# LPC_Female_FMC.net
KiCad netlist of a schematic drawn in Altium Designer
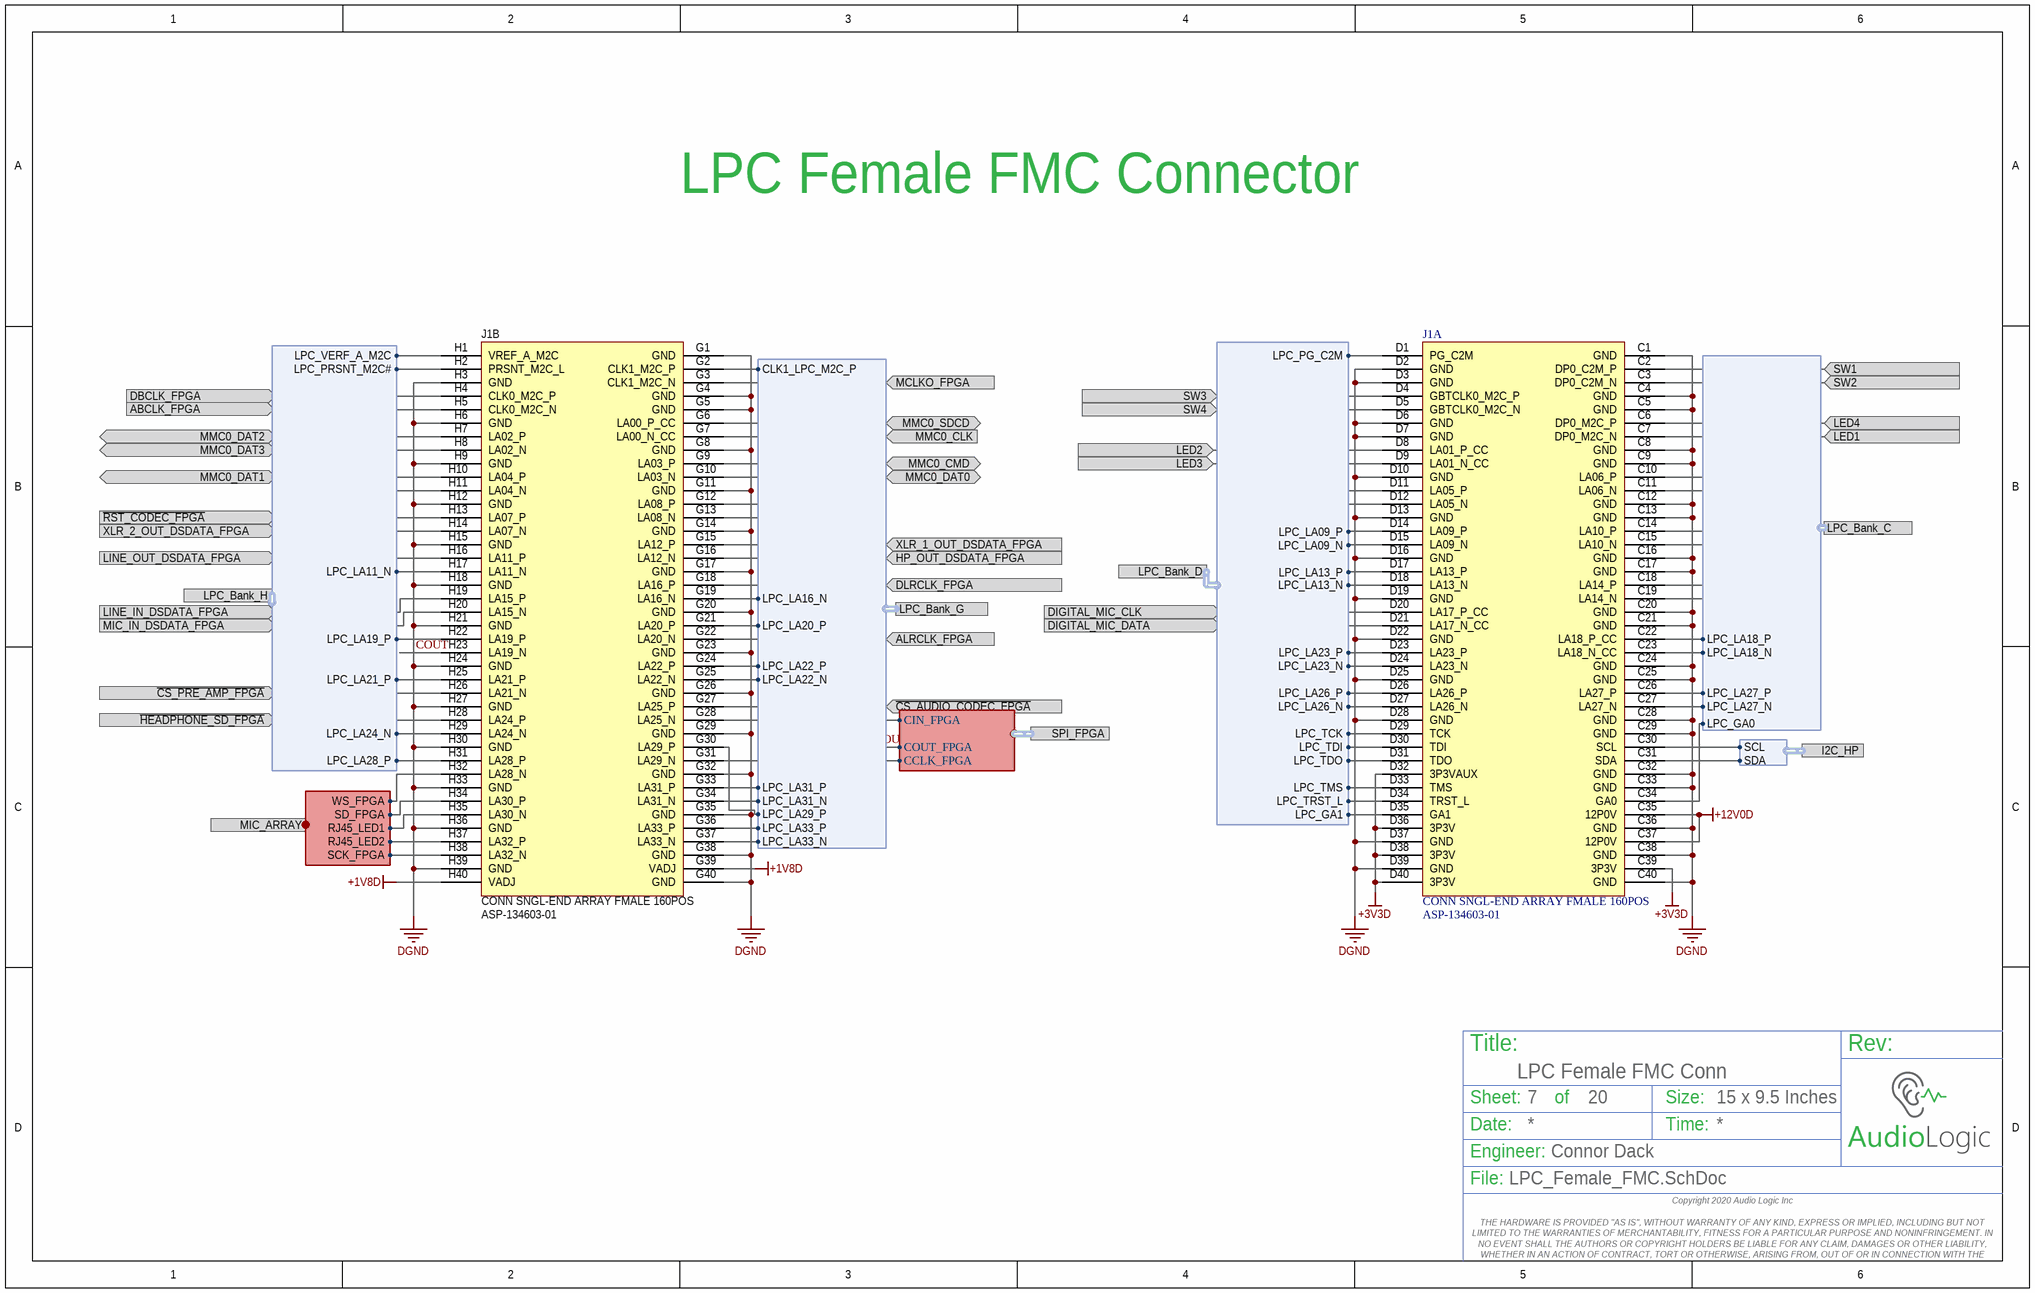
[diagram p0: LPC_Female_FMC.SchDoc]

(export (version "E")
  (design (tool "Eeschema 10.0.6"))
  (components
    (comp (ref "J1")
      (value "CONN SNGL-END ARRAY FMALE 160POS")
      (footprint "ASP-134603-01")
      (description "Low Pin Count Female FPGA Mezzanine Card Connector")
      (fields
        (field (name "MANUFACTURER") "Samtec")
        (field (name "MANUFACTURER PART NUMBER") "ASP-134603-01")
      )
      (libsource (lib "Schematic_Components_CD") (part "ASP-134603-01"))
    )
  )
  (nets
    (net (code "9") (name "+1V8D") (class "Default")
      (node (ref "J1") (pin "G39") (pinfunction "VADJ_G39") (pintype "power_in"))
      (node (ref "J1") (pin "H40") (pinfunction "VADJ_H40") (pintype "power_in"))
    )
    (net (code "10") (name "+3V3D") (class "Default")
      (node (ref "J1") (pin "C39") (pinfunction "3P3V_C39") (pintype "power_in"))
      (node (ref "J1") (pin "D32") (pinfunction "3P3VAUX_D32") (pintype "power_in"))
      (node (ref "J1") (pin "D36") (pinfunction "3P3V_D36") (pintype "power_in"))
      (node (ref "J1") (pin "D38") (pinfunction "3P3V_D38") (pintype "power_in"))
      (node (ref "J1") (pin "D40") (pinfunction "3P3V_D40") (pintype "power_in"))
    )
    (net (code "11") (name "+12V0D") (class "Default")
      (node (ref "J1") (pin "C10") (pinfunction "LA06_P_C10") (pintype "passive"))
      (node (ref "J1") (pin "C11") (pinfunction "LA06_N_C11") (pintype "passive"))
      (node (ref "J1") (pin "C35") (pinfunction "12P0V_C35") (pintype "power_in"))
      (node (ref "J1") (pin "C37") (pinfunction "12P0V_C37") (pintype "power_in"))
      (node (ref "J1") (pin "D11") (pinfunction "LA05_P_D11") (pintype "passive"))
      (node (ref "J1") (pin "D12") (pinfunction "LA05_N_D12") (pintype "passive"))
      (node (ref "J1") (pin "G12") (pinfunction "LA08_P_G12") (pintype "passive"))
      (node (ref "J1") (pin "G13") (pinfunction "LA08_N_G13") (pintype "passive"))
      (node (ref "J1") (pin "H11") (pinfunction "LA04_N_H11") (pintype "passive"))
    )
    (net (code "12") (name "/ABCLK_FPGA") (class "Default")
      (node (ref "J1") (pin "H5") (pinfunction "CLK0_M2C_N_H5") (pintype "passive"))
    )
    (net (code "13") (name "/ALRCLK_FPGA") (class "Default")
      (node (ref "J1") (pin "G22") (pinfunction "LA20_N_G22") (pintype "passive"))
    )
    (net (code "14") (name "/CCLK_FPGA") (class "Default")
      (node (ref "J1") (pin "G31") (pinfunction "LA29_N_G31") (pintype "passive"))
    )
    (net (code "15") (name "/CIN_FPGA") (class "Default")
      (node (ref "J1") (pin "G28") (pinfunction "LA25_N_G28") (pintype "passive"))
    )
    (net (code "16") (name "/CLK1_LPC_M2C_P") (class "Default")
      (node (ref "J1") (pin "G2") (pinfunction "CLK1_M2C_P_G2") (pintype "passive"))
    )
    (net (code "17") (name "/CMD_DIR1") (class "Default")
      (node (ref "J1") (pin "C19") (pinfunction "LA14_N_C19") (pintype "passive"))
    )
    (net (code "18") (name "/CMD_DIR2") (class "Default")
      (node (ref "J1") (pin "C18") (pinfunction "LA14_P_C18") (pintype "passive"))
    )
    (net (code "19") (name "/COUT") (class "Default")
      (node (ref "J1") (pin "H23") (pinfunction "LA19_N_H23") (pintype "passive"))
    )
    (net (code "20") (name "/DATA_DIR1") (class "Default")
      (node (ref "J1") (pin "C15") (pinfunction "LA10_N_C15") (pintype "passive"))
    )
    (net (code "21") (name "/DATA_DIR2") (class "Default")
      (node (ref "J1") (pin "C14") (pinfunction "LA10_P_C14") (pintype "passive"))
    )
    (net (code "22") (name "/DBCLK_FPGA") (class "Default")
      (node (ref "J1") (pin "H4") (pinfunction "CLK0_M2C_P_H4") (pintype "passive"))
    )
    (net (code "23") (name "/DIGITAL_MIC_CLK") (class "Default")
      (node (ref "J1") (pin "D20") (pinfunction "LA17_P_CC_D20") (pintype "passive"))
    )
    (net (code "24") (name "/DIGITAL_MIC_DATA") (class "Default")
      (node (ref "J1") (pin "D21") (pinfunction "LA17_N_CC_D21") (pintype "passive"))
    )
    (net (code "25") (name "/DLRCLK_FPGA") (class "Default")
      (node (ref "J1") (pin "G18") (pinfunction "LA16_P_G18") (pintype "passive"))
    )
    (net (code "26") (name "/HP_OUT_DSDATA_FPGA") (class "Default")
      (node (ref "J1") (pin "G16") (pinfunction "LA12_N_G16") (pintype "passive"))
    )
    (net (code "27") (name "/LED1") (class "Default")
      (node (ref "J1") (pin "C7") (pinfunction "DP0_M2C_N_C7") (pintype "passive"))
    )
    (net (code "28") (name "/LED2") (class "Default")
      (node (ref "J1") (pin "D8") (pinfunction "LA01_P_CC_D8") (pintype "passive"))
    )
    (net (code "29") (name "/LED3") (class "Default")
      (node (ref "J1") (pin "D9") (pinfunction "LA01_N_CC_D9") (pintype "passive"))
    )
    (net (code "30") (name "/LED4") (class "Default")
      (node (ref "J1") (pin "C6") (pinfunction "DP0_M2C_P_C6") (pintype "passive"))
    )
    (net (code "31") (name "/LINE_IN_DSDATA_FPGA") (class "Default")
      (node (ref "J1") (pin "H19") (pinfunction "LA15_P_H19") (pintype "passive"))
    )
    (net (code "32") (name "/LINE_OUT_DSDATA_FPGA") (class "Default")
      (node (ref "J1") (pin "H16") (pinfunction "LA11_P_H16") (pintype "passive"))
    )
    (net (code "33") (name "/LPC_GA0") (class "Default")
      (node (ref "J1") (pin "C34") (pinfunction "GA0_C34") (pintype "passive"))
    )
    (net (code "34") (name "/LPC_GA1") (class "Default")
      (node (ref "J1") (pin "D35") (pinfunction "GA1_D35") (pintype "passive"))
    )
    (net (code "35") (name "/LPC_LA09_N") (class "Default")
      (node (ref "J1") (pin "D15") (pinfunction "LA09_N_D15") (pintype "passive"))
    )
    (net (code "36") (name "/LPC_LA09_P") (class "Default")
      (node (ref "J1") (pin "D14") (pinfunction "LA09_P_D14") (pintype "passive"))
    )
    (net (code "37") (name "/LPC_LA11_N") (class "Default")
      (node (ref "J1") (pin "H17") (pinfunction "LA11_N_H17") (pintype "passive"))
    )
    (net (code "38") (name "/LPC_LA13_N") (class "Default")
      (node (ref "J1") (pin "D18") (pinfunction "LA13_N_D18") (pintype "passive"))
    )
    (net (code "39") (name "/LPC_LA13_P") (class "Default")
      (node (ref "J1") (pin "D17") (pinfunction "LA13_P_D17") (pintype "passive"))
    )
    (net (code "40") (name "/LPC_LA16_N") (class "Default")
      (node (ref "J1") (pin "G19") (pinfunction "LA16_N_G19") (pintype "passive"))
    )
    (net (code "41") (name "/LPC_LA18_N") (class "Default")
      (node (ref "J1") (pin "C23") (pinfunction "LA18_N_CC_C23") (pintype "passive"))
    )
    (net (code "42") (name "/LPC_LA18_P") (class "Default")
      (node (ref "J1") (pin "C22") (pinfunction "LA18_P_CC_C22") (pintype "passive"))
    )
    (net (code "43") (name "/LPC_LA19_P") (class "Default")
      (node (ref "J1") (pin "H22") (pinfunction "LA19_P_H22") (pintype "passive"))
    )
    (net (code "44") (name "/LPC_LA20_P") (class "Default")
      (node (ref "J1") (pin "G21") (pinfunction "LA20_P_G21") (pintype "passive"))
    )
    (net (code "45") (name "/LPC_LA21_P") (class "Default")
      (node (ref "J1") (pin "H25") (pinfunction "LA21_P_H25") (pintype "passive"))
    )
    (net (code "46") (name "/LPC_LA22_N") (class "Default")
      (node (ref "J1") (pin "G25") (pinfunction "LA22_N_G25") (pintype "passive"))
    )
    (net (code "47") (name "/LPC_LA22_P") (class "Default")
      (node (ref "J1") (pin "G24") (pinfunction "LA22_P_G24") (pintype "passive"))
    )
    (net (code "48") (name "/LPC_LA23_N") (class "Default")
      (node (ref "J1") (pin "D24") (pinfunction "LA23_N_D24") (pintype "passive"))
    )
    (net (code "49") (name "/LPC_LA23_P") (class "Default")
      (node (ref "J1") (pin "D23") (pinfunction "LA23_P_D23") (pintype "passive"))
    )
    (net (code "50") (name "/LPC_LA24_N") (class "Default")
      (node (ref "J1") (pin "H29") (pinfunction "LA24_N_H29") (pintype "passive"))
    )
    (net (code "51") (name "/LPC_LA26_N") (class "Default")
      (node (ref "J1") (pin "D27") (pinfunction "LA26_N_D27") (pintype "passive"))
    )
    (net (code "52") (name "/LPC_LA26_P") (class "Default")
      (node (ref "J1") (pin "D26") (pinfunction "LA26_P_D26") (pintype "passive"))
    )
    (net (code "53") (name "/LPC_LA27_N") (class "Default")
      (node (ref "J1") (pin "C27") (pinfunction "LA27_N_C27") (pintype "passive"))
    )
    (net (code "54") (name "/LPC_LA27_P") (class "Default")
      (node (ref "J1") (pin "C26") (pinfunction "LA27_P_C26") (pintype "passive"))
    )
    (net (code "55") (name "/LPC_LA28_P") (class "Default")
      (node (ref "J1") (pin "H31") (pinfunction "LA28_P_H31") (pintype "passive"))
    )
    (net (code "56") (name "/LPC_LA29_P") (class "Default")
      (node (ref "J1") (pin "G30") (pinfunction "LA29_P_G30") (pintype "passive"))
    )
    (net (code "57") (name "/LPC_LA31_N") (class "Default")
      (node (ref "J1") (pin "G34") (pinfunction "LA31_N_G34") (pintype "passive"))
    )
    (net (code "58") (name "/LPC_LA31_P") (class "Default")
      (node (ref "J1") (pin "G33") (pinfunction "LA31_P_G33") (pintype "passive"))
    )
    (net (code "59") (name "/LPC_LA33_N") (class "Default")
      (node (ref "J1") (pin "G37") (pinfunction "LA33_N_G37") (pintype "passive"))
    )
    (net (code "60") (name "/LPC_LA33_P") (class "Default")
      (node (ref "J1") (pin "G36") (pinfunction "LA33_P_G36") (pintype "passive"))
    )
    (net (code "61") (name "/LPC_PG_C2M") (class "Default")
      (node (ref "J1") (pin "D1") (pinfunction "PG_C2M_D1") (pintype "passive"))
    )
    (net (code "62") (name "/LPC_PRSNT_M2C#") (class "Default")
      (node (ref "J1") (pin "H2") (pinfunction "PRSNT_M2C_L_H2") (pintype "passive"))
    )
    (net (code "63") (name "/LPC_TCK") (class "Default")
      (node (ref "J1") (pin "D29") (pinfunction "TCK_D29") (pintype "passive"))
    )
    (net (code "64") (name "/LPC_TDI") (class "Default")
      (node (ref "J1") (pin "D30") (pinfunction "TDI_D30") (pintype "passive"))
    )
    (net (code "65") (name "/LPC_TDO") (class "Default")
      (node (ref "J1") (pin "D31") (pinfunction "TDO_D31") (pintype "passive"))
    )
    (net (code "66") (name "/LPC_TMS") (class "Default")
      (node (ref "J1") (pin "D33") (pinfunction "TMS_D33") (pintype "passive"))
    )
    (net (code "67") (name "/LPC_TRST_L") (class "Default")
      (node (ref "J1") (pin "D34") (pinfunction "TRST_L_D34") (pintype "passive"))
    )
    (net (code "68") (name "/LPC_VERF_A_M2C") (class "Default")
      (node (ref "J1") (pin "H1") (pinfunction "VREF_A_M2C_H1") (pintype "power_in"))
    )
    (net (code "69") (name "/MCLKO_FPGA") (class "Default")
      (node (ref "J1") (pin "G3") (pinfunction "CLK1_M2C_N_G3") (pintype "passive"))
    )
    (net (code "70") (name "/MIC_IN_DSDATA_FPGA") (class "Default")
      (node (ref "J1") (pin "H20") (pinfunction "LA15_N_H20") (pintype "passive"))
    )
    (net (code "71") (name "/MMC0_CLK") (class "Default")
      (node (ref "J1") (pin "G7") (pinfunction "LA00_N_CC_G7") (pintype "passive"))
    )
    (net (code "72") (name "/MMC0_CMD") (class "Default")
      (node (ref "J1") (pin "G9") (pinfunction "LA03_P_G9") (pintype "passive"))
    )
    (net (code "73") (name "/MMC0_DAT0") (class "Default")
      (node (ref "J1") (pin "G10") (pinfunction "LA03_N_G10") (pintype "passive"))
    )
    (net (code "74") (name "/MMC0_DAT1") (class "Default")
      (node (ref "J1") (pin "H10") (pinfunction "LA04_P_H10") (pintype "passive"))
    )
    (net (code "75") (name "/MMC0_DAT2") (class "Default")
      (node (ref "J1") (pin "H7") (pinfunction "LA02_P_H7") (pintype "passive"))
    )
    (net (code "76") (name "/MMC0_DAT3") (class "Default")
      (node (ref "J1") (pin "H8") (pinfunction "LA02_N_H8") (pintype "passive"))
    )
    (net (code "77") (name "/MMC0_SDCD") (class "Default")
      (node (ref "J1") (pin "G6") (pinfunction "LA00_P_CC_G6") (pintype "passive"))
    )
    (net (code "78") (name "/RJ45_LED1") (class "Default")
      (node (ref "J1") (pin "H35") (pinfunction "LA30_N_H35") (pintype "passive"))
    )
    (net (code "79") (name "/RJ45_LED2") (class "Default")
      (node (ref "J1") (pin "H37") (pinfunction "LA32_P_H37") (pintype "passive"))
    )
    (net (code "80") (name "/SCK_FPGA") (class "Default")
      (node (ref "J1") (pin "H38") (pinfunction "LA32_N_H38") (pintype "passive"))
    )
    (net (code "81") (name "/SCL") (class "Default")
      (node (ref "J1") (pin "C30") (pinfunction "SCL_C30") (pintype "passive"))
    )
    (net (code "82") (name "/SDA") (class "Default")
      (node (ref "J1") (pin "C31") (pinfunction "SDA_C31") (pintype "passive"))
    )
    (net (code "83") (name "/SD_FPGA") (class "Default")
      (node (ref "J1") (pin "H34") (pinfunction "LA30_P_H34") (pintype "passive"))
    )
    (net (code "84") (name "/SW1") (class "Default")
      (node (ref "J1") (pin "C2") (pinfunction "DP0_C2M_P_C2") (pintype "passive"))
    )
    (net (code "85") (name "/SW2") (class "Default")
      (node (ref "J1") (pin "C3") (pinfunction "DP0_C2M_N_C3") (pintype "passive"))
    )
    (net (code "86") (name "/SW3") (class "Default")
      (node (ref "J1") (pin "D4") (pinfunction "GBTCLK0_M2C_P_D4") (pintype "passive"))
    )
    (net (code "87") (name "/SW4") (class "Default")
      (node (ref "J1") (pin "D5") (pinfunction "GBTCLK0_M2C_N_D5") (pintype "passive"))
    )
    (net (code "88") (name "/WS_FPGA") (class "Default")
      (node (ref "J1") (pin "H32") (pinfunction "LA28_N_H32") (pintype "passive"))
    )
    (net (code "89") (name "/XLR_1_OUT_DSDATA_FPGA") (class "Default")
      (node (ref "J1") (pin "G15") (pinfunction "LA12_P_G15") (pintype "passive"))
    )
    (net (code "90") (name "/XLR_2_OUT_DSDATA_FPGA") (class "Default")
      (node (ref "J1") (pin "H14") (pinfunction "LA07_N_H14") (pintype "passive"))
    )
    (net (code "98") (name "/~{CS_AUDIO_CODEC_FPGA}") (class "Default")
      (node (ref "J1") (pin "G27") (pinfunction "LA25_P_G27") (pintype "passive"))
    )
    (net (code "99") (name "/~{CS_PRE_AMP_FPGA}") (class "Default")
      (node (ref "J1") (pin "H26") (pinfunction "LA21_N_H26") (pintype "passive"))
    )
    (net (code "100") (name "/~{HEADPHONE_SD_FPGA}") (class "Default")
      (node (ref "J1") (pin "H28") (pinfunction "LA24_P_H28") (pintype "passive"))
    )
    (net (code "101") (name "/~{RST_CODEC_FPGA}") (class "Default")
      (node (ref "J1") (pin "H13") (pinfunction "LA07_P_H13") (pintype "passive"))
    )
    (net (code "102") (name "DGND") (class "Default")
      (node (ref "J1") (pin "C1") (pinfunction "GND_C1") (pintype "power_in"))
      (node (ref "J1") (pin "C12") (pinfunction "GND_C12") (pintype "power_in"))
      (node (ref "J1") (pin "C13") (pinfunction "GND_C13") (pintype "power_in"))
      (node (ref "J1") (pin "C16") (pinfunction "GND_C16") (pintype "power_in"))
      (node (ref "J1") (pin "C17") (pinfunction "GND_C17") (pintype "power_in"))
      (node (ref "J1") (pin "C20") (pinfunction "GND_C20") (pintype "power_in"))
      (node (ref "J1") (pin "C21") (pinfunction "GND_C21") (pintype "power_in"))
      (node (ref "J1") (pin "C24") (pinfunction "GND_C24") (pintype "power_in"))
      (node (ref "J1") (pin "C25") (pinfunction "GND_C25") (pintype "power_in"))
      (node (ref "J1") (pin "C28") (pinfunction "GND_C28") (pintype "power_in"))
      (node (ref "J1") (pin "C29") (pinfunction "GND_C29") (pintype "power_in"))
      (node (ref "J1") (pin "C32") (pinfunction "GND_C32") (pintype "power_in"))
      (node (ref "J1") (pin "C33") (pinfunction "GND_C33") (pintype "power_in"))
      (node (ref "J1") (pin "C36") (pinfunction "GND_C36") (pintype "power_in"))
      (node (ref "J1") (pin "C38") (pinfunction "GND_C38") (pintype "power_in"))
      (node (ref "J1") (pin "C4") (pinfunction "GND_C4") (pintype "power_in"))
      (node (ref "J1") (pin "C40") (pinfunction "GND_C40") (pintype "power_in"))
      (node (ref "J1") (pin "C5") (pinfunction "GND_C5") (pintype "power_in"))
      (node (ref "J1") (pin "C8") (pinfunction "GND_C8") (pintype "power_in"))
      (node (ref "J1") (pin "C9") (pinfunction "GND_C9") (pintype "power_in"))
      (node (ref "J1") (pin "D10") (pinfunction "GND_D10") (pintype "power_in"))
      (node (ref "J1") (pin "D13") (pinfunction "GND_D13") (pintype "power_in"))
      (node (ref "J1") (pin "D16") (pinfunction "GND_D16") (pintype "power_in"))
      (node (ref "J1") (pin "D19") (pinfunction "GND_D19") (pintype "power_in"))
      (node (ref "J1") (pin "D2") (pinfunction "GND_D2") (pintype "power_in"))
      (node (ref "J1") (pin "D22") (pinfunction "GND_D22") (pintype "power_in"))
      (node (ref "J1") (pin "D25") (pinfunction "GND_D25") (pintype "power_in"))
      (node (ref "J1") (pin "D28") (pinfunction "GND_D28") (pintype "power_in"))
      (node (ref "J1") (pin "D3") (pinfunction "GND_D3") (pintype "power_in"))
      (node (ref "J1") (pin "D37") (pinfunction "GND_D37") (pintype "power_in"))
      (node (ref "J1") (pin "D39") (pinfunction "GND_D39") (pintype "power_in"))
      (node (ref "J1") (pin "D6") (pinfunction "GND_D6") (pintype "power_in"))
      (node (ref "J1") (pin "D7") (pinfunction "GND_D7") (pintype "power_in"))
      (node (ref "J1") (pin "G1") (pinfunction "GND_G1") (pintype "power_in"))
      (node (ref "J1") (pin "G11") (pinfunction "GND_G11") (pintype "power_in"))
      (node (ref "J1") (pin "G14") (pinfunction "GND_G14") (pintype "power_in"))
      (node (ref "J1") (pin "G17") (pinfunction "GND_G17") (pintype "power_in"))
      (node (ref "J1") (pin "G20") (pinfunction "GND_G20") (pintype "power_in"))
      (node (ref "J1") (pin "G23") (pinfunction "GND_G23") (pintype "power_in"))
      (node (ref "J1") (pin "G26") (pinfunction "GND_G26") (pintype "power_in"))
      (node (ref "J1") (pin "G29") (pinfunction "GND_G29") (pintype "power_in"))
      (node (ref "J1") (pin "G32") (pinfunction "GND_G32") (pintype "power_in"))
      (node (ref "J1") (pin "G35") (pinfunction "GND_G35") (pintype "power_in"))
      (node (ref "J1") (pin "G38") (pinfunction "GND_G38") (pintype "power_in"))
      (node (ref "J1") (pin "G4") (pinfunction "GND_G4") (pintype "power_in"))
      (node (ref "J1") (pin "G40") (pinfunction "GND_G40") (pintype "power_in"))
      (node (ref "J1") (pin "G5") (pinfunction "GND_G5") (pintype "power_in"))
      (node (ref "J1") (pin "G8") (pinfunction "GND_G8") (pintype "power_in"))
      (node (ref "J1") (pin "H12") (pinfunction "GND_H12") (pintype "power_in"))
      (node (ref "J1") (pin "H15") (pinfunction "GND_H15") (pintype "power_in"))
      (node (ref "J1") (pin "H18") (pinfunction "GND_H18") (pintype "power_in"))
      (node (ref "J1") (pin "H21") (pinfunction "GND_H21") (pintype "power_in"))
      (node (ref "J1") (pin "H24") (pinfunction "GND_H24") (pintype "power_in"))
      (node (ref "J1") (pin "H27") (pinfunction "GND_H27") (pintype "power_in"))
      (node (ref "J1") (pin "H3") (pinfunction "GND_H3") (pintype "power_in"))
      (node (ref "J1") (pin "H30") (pinfunction "GND_H30") (pintype "power_in"))
      (node (ref "J1") (pin "H33") (pinfunction "GND_H33") (pintype "power_in"))
      (node (ref "J1") (pin "H36") (pinfunction "GND_H36") (pintype "power_in"))
      (node (ref "J1") (pin "H39") (pinfunction "GND_H39") (pintype "power_in"))
      (node (ref "J1") (pin "H6") (pinfunction "GND_H6") (pintype "power_in"))
      (node (ref "J1") (pin "H9") (pinfunction "GND_H9") (pintype "power_in"))
    )
  )
)
